# MC-test-simple.net
KiCad netlist of a schematic drawn in EAGLE
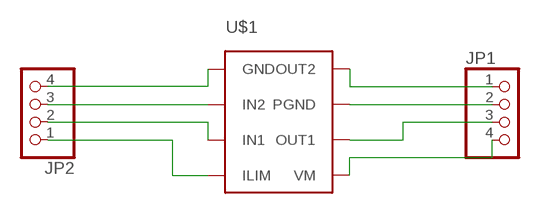
[diagram p0: schematic, sheet 1]

(export (version "E")
  (design (tool "Eeschema 10.0.6"))
  (components
    (comp (ref "JP1")
      (value "PINHD-1X4")
      (footprint "eagle-import:1X04")
      (libsource (lib "eagle-import") (part "PINHD-1X4"))
    )
    (comp (ref "JP2")
      (value "PINHD-1X4")
      (footprint "eagle-import:1X04")
      (libsource (lib "eagle-import") (part "PINHD-1X4"))
    )
    (comp (ref "U$1")
      (value "DRV8871")
      (footprint "eagle-import:SO-8_POWERPAD")
      (libsource (lib "eagle-import") (part "DRV8871"))
    )
  )
  (nets
    (net (code "1") (name "/GND") (class "Default")
      (node (ref "JP1") (pin "2") (pinfunction "2_2") (pintype "passive"))
      (node (ref "JP2") (pin "4") (pinfunction "4_4") (pintype "passive"))
      (node (ref "U$1") (pin "1") (pinfunction "GND_1") (pintype "power_in"))
      (node (ref "U$1") (pin "7") (pinfunction "PGND_7") (pintype "power_in"))
    )
    (net (code "2") (name "Net-(U$1-ILIM)") (class "Default")
      (node (ref "JP2") (pin "1") (pinfunction "1_1") (pintype "passive"))
      (node (ref "U$1") (pin "4") (pinfunction "ILIM_4") (pintype "input"))
    )
    (net (code "3") (name "Net-(U$1-IN1)") (class "Default")
      (node (ref "JP2") (pin "2") (pinfunction "2_2") (pintype "passive"))
      (node (ref "U$1") (pin "3") (pinfunction "IN1_3") (pintype "input"))
    )
    (net (code "4") (name "Net-(U$1-IN2)") (class "Default")
      (node (ref "JP2") (pin "3") (pinfunction "3_3") (pintype "passive"))
      (node (ref "U$1") (pin "2") (pinfunction "IN2_2") (pintype "input"))
    )
    (net (code "5") (name "Net-(U$1-OUT1)") (class "Default")
      (node (ref "JP1") (pin "3") (pinfunction "3_3") (pintype "passive"))
      (node (ref "U$1") (pin "6") (pinfunction "OUT1_6") (pintype "output"))
    )
    (net (code "6") (name "Net-(U$1-OUT2)") (class "Default")
      (node (ref "JP1") (pin "1") (pinfunction "1_1") (pintype "passive"))
      (node (ref "U$1") (pin "8") (pinfunction "OUT2_8") (pintype "output"))
    )
    (net (code "7") (name "Net-(U$1-VM)") (class "Default")
      (node (ref "JP1") (pin "4") (pinfunction "4_4") (pintype "passive"))
      (node (ref "U$1") (pin "5") (pinfunction "VM_5") (pintype "power_in"))
    )
  )
)
